# breakout_proto-checkup.net
KiCad netlist of a schematic drawn in EAGLE
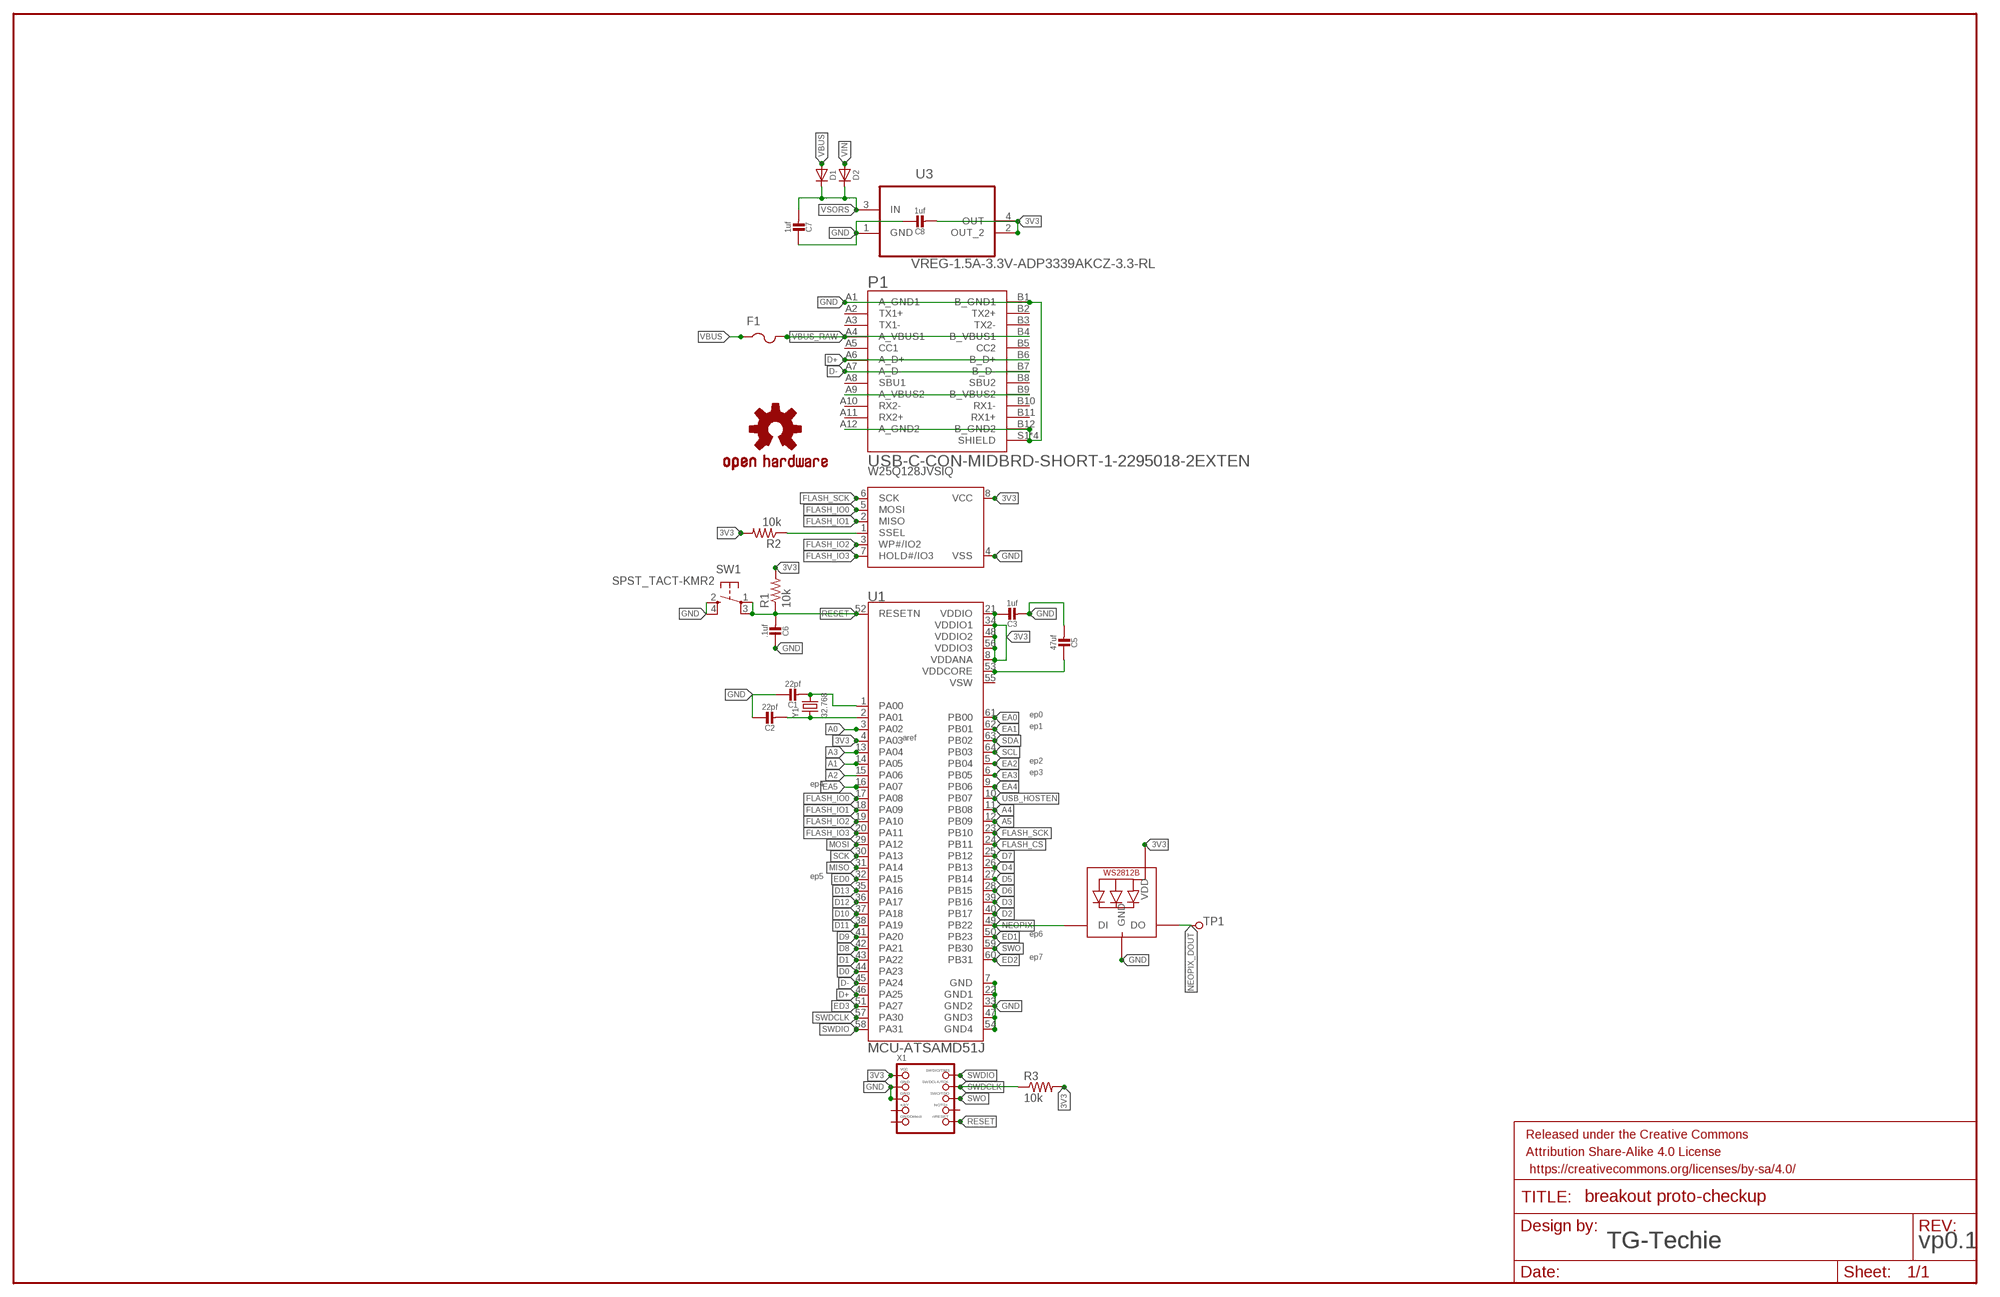
[diagram p0: schematic, sheet 1]

(export (version "E")
  (design (tool "Eeschema 10.0.6"))
  (components
    (comp (ref "C1")
      (value "22pf")
      (footprint "eagle-import:MICROBUILDER__0805")
      (libsource (lib "eagle-import") (part "C-US__0805"))
    )
    (comp (ref "C2")
      (value "22pf")
      (footprint "eagle-import:MICROBUILDER__0805")
      (libsource (lib "eagle-import") (part "C-US__0805"))
    )
    (comp (ref "C3")
      (value "1uf")
      (footprint "eagle-import:MICROBUILDER__0805")
      (libsource (lib "eagle-import") (part "C-US__0805"))
    )
    (comp (ref "C5")
      (value "47uf")
      (footprint "eagle-import:MICROBUILDER__0805")
      (libsource (lib "eagle-import") (part "C-US__0805"))
    )
    (comp (ref "C6")
      (value ".1uf")
      (footprint "eagle-import:MICROBUILDER__0805")
      (libsource (lib "eagle-import") (part "C-US__0805"))
    )
    (comp (ref "C7")
      (value "1uf")
      (footprint "eagle-import:MICROBUILDER__0805")
      (libsource (lib "eagle-import") (part "C-US__0805"))
    )
    (comp (ref "C8")
      (value "1uf")
      (footprint "eagle-import:MICROBUILDER__0805")
      (libsource (lib "eagle-import") (part "C-US__0805"))
    )
    (comp (ref "D1")
      (value "DIODESOD-123")
      (footprint "eagle-import:SOD-123")
      (libsource (lib "eagle-import") (part "DIODESOD-123"))
    )
    (comp (ref "D2")
      (value "DIODESOD-123")
      (footprint "eagle-import:SOD-123")
      (libsource (lib "eagle-import") (part "DIODESOD-123"))
    )
    (comp (ref "F1")
      (value "PTCFUSE-1206")
      (footprint "eagle-import:R1206")
      (libsource (lib "eagle-import") (part "PTCFUSE-1206"))
    )
    (comp (ref "FRAME1")
      (value "FRAME-LEDGER")
      (footprint "eagle-import:CREATIVE_COMMONS")
      (libsource (lib "eagle-import") (part "FRAME-LEDGER"))
    )
    (comp (ref "LED1")
      (value "LED-NEO-WS2812B3535")
      (footprint "eagle-import:LED3535")
      (libsource (lib "eagle-import") (part "LED-NEO-WS2812B3535"))
    )
    (comp (ref "LOGO1")
      (value "OSHW-LOGOMINI")
      (footprint "eagle-import:OSHW-LOGO-MINI")
      (libsource (lib "eagle-import") (part "OSHW-LOGOMINI"))
    )
    (comp (ref "P1")
      (value "USB-C-CON-MIDBRD-SHORT-1-2295018-2EXTEN")
      (footprint "eagle-import:TE_1-2295018-2_EXTEN")
      (libsource (lib "eagle-import") (part "USB-C-CON-MIDBRD-SHORT-1-2295018-2EXTEN"))
    )
    (comp (ref "R1")
      (value "10k")
      (footprint "eagle-import:R0805")
      (libsource (lib "eagle-import") (part "R-US_R0805"))
    )
    (comp (ref "R2")
      (value "10k")
      (footprint "eagle-import:R0805")
      (libsource (lib "eagle-import") (part "R-US_R0805"))
    )
    (comp (ref "R3")
      (value "10k")
      (footprint "eagle-import:R0805")
      (libsource (lib "eagle-import") (part "R-US_R0805"))
    )
    (comp (ref "SW1")
      (value "SPST_TACT-KMR2")
      (footprint "eagle-import:KMR2")
      (libsource (lib "eagle-import") (part "SPST_TACT-KMR2"))
    )
    (comp (ref "TP1")
      (value "TESTPOINT_1X1")
      (footprint "eagle-import:1X1_POGO")
      (libsource (lib "eagle-import") (part "TESTPOINT_1X1"))
    )
    (comp (ref "U1")
      (value "MCU-ATSAMD51J")
      (footprint "eagle-import:QFP50P1200X1200X120-64N")
      (fields (field (name "MF") "Microchip") (field (name "MP") "ATSAMD51J20A-AU"))
      (libsource (lib "eagle-import") (part "MCU-ATSAMD51J"))
    )
    (comp (ref "U3")
      (value "VREG-1.5A-3.3V-ADP3339AKCZ-3.3-RL")
      (footprint "eagle-import:SOT230P700X180-4N")
      (fields (field (name "MF") "Analog Devices") (field (name "MP") "ADP3339AKCZ-3.3-RL"))
      (libsource (lib "eagle-import") (part "VREG-1.5A-3.3V-ADP3339AKCZ-3.3-RL"))
    )
    (comp (ref "W25Q128JVSIQ")
      (value "FLASH-SPI-SOIC8208MIL")
      (footprint "eagle-import:SOIC8_208MIL")
      (libsource (lib "eagle-import") (part "FLASH-SPI-SOIC8208MIL"))
    )
    (comp (ref "X1")
      (value "INTRFC-JTAG-CORTEXBOXPOSTS")
      (footprint "eagle-import:2X05_1.27MM_BOX_POSTS")
      (libsource (lib "eagle-import") (part "INTRFC-JTAG-CORTEXBOXPOSTS"))
    )
    (comp (ref "Y1")
      (value "32.768")
      (footprint "eagle-import:MICROBUILDER_CRYSTAL_4.9X1.8")
      (libsource (lib "eagle-import") (part "XTAL_ADA4.9X1.8"))
    )
  )
  (nets
    (net (code "1") (name "/VSW") (class "Default")
      (node (ref "U1") (pin "55") (pinfunction "VSW_55") (pintype "power_in"))
    )
    (net (code "2") (name "3V3") (class "Default")
      (node (ref "C3") (pin "1") (pinfunction "1_1") (pintype "passive"))
      (node (ref "C8") (pin "2") (pinfunction "2_2") (pintype "passive"))
      (node (ref "LED1") (pin "2") (pinfunction "VDD_2") (pintype "power_in"))
      (node (ref "R1") (pin "2") (pinfunction "2_2") (pintype "passive"))
      (node (ref "R2") (pin "2") (pinfunction "2_2") (pintype "passive"))
      (node (ref "R3") (pin "2") (pinfunction "2_2") (pintype "passive"))
      (node (ref "U1") (pin "21") (pinfunction "VDDIO_21") (pintype "power_in"))
      (node (ref "U1") (pin "34") (pinfunction "VDDIO1_34") (pintype "power_in"))
      (node (ref "U1") (pin "4") (pinfunction "PA03_4") (pintype "bidirectional"))
      (node (ref "U1") (pin "48") (pinfunction "VDDIO2_48") (pintype "power_in"))
      (node (ref "U1") (pin "56") (pinfunction "VDDIO3_56") (pintype "power_in"))
      (node (ref "U1") (pin "8") (pinfunction "VDDANA_8") (pintype "power_in"))
      (node (ref "U3") (pin "2") (pinfunction "OUT_2_2") (pintype "output"))
      (node (ref "U3") (pin "4") (pinfunction "OUT_4") (pintype "output"))
      (node (ref "W25Q128JVSIQ") (pin "8") (pinfunction "VCC_8") (pintype "bidirectional"))
      (node (ref "X1") (pin "1") (pinfunction "VCC_1") (pintype "power_in"))
    )
    (net (code "3") (name "A0") (class "Default")
      (node (ref "U1") (pin "3") (pinfunction "PA02_3") (pintype "bidirectional"))
    )
    (net (code "4") (name "A1") (class "Default")
      (node (ref "U1") (pin "14") (pinfunction "PA05_14") (pintype "bidirectional"))
    )
    (net (code "5") (name "A2") (class "Default")
      (node (ref "U1") (pin "15") (pinfunction "PA06_15") (pintype "bidirectional"))
    )
    (net (code "6") (name "A3") (class "Default")
      (node (ref "U1") (pin "13") (pinfunction "PA04_13") (pintype "bidirectional"))
    )
    (net (code "7") (name "A4") (class "Default")
      (node (ref "U1") (pin "11") (pinfunction "PB08_11") (pintype "bidirectional"))
    )
    (net (code "8") (name "A5") (class "Default")
      (node (ref "U1") (pin "12") (pinfunction "PB09_12") (pintype "bidirectional"))
    )
    (net (code "9") (name "D+") (class "Default")
      (node (ref "P1") (pin "A6") (pinfunction "A_D+_A6") (pintype "passive"))
      (node (ref "P1") (pin "B6") (pinfunction "B_D+_B6") (pintype "passive"))
      (node (ref "U1") (pin "46") (pinfunction "PA25_46") (pintype "bidirectional"))
    )
    (net (code "10") (name "D-") (class "Default")
      (node (ref "P1") (pin "A7") (pinfunction "A_D-_A7") (pintype "passive"))
      (node (ref "P1") (pin "B7") (pinfunction "B_D-_B7") (pintype "passive"))
      (node (ref "U1") (pin "45") (pinfunction "PA24_45") (pintype "bidirectional"))
    )
    (net (code "11") (name "D0") (class "Default")
      (node (ref "U1") (pin "44") (pinfunction "PA23_44") (pintype "bidirectional"))
    )
    (net (code "12") (name "D1") (class "Default")
      (node (ref "U1") (pin "43") (pinfunction "PA22_43") (pintype "bidirectional"))
    )
    (net (code "13") (name "D2") (class "Default")
      (node (ref "U1") (pin "40") (pinfunction "PB17_40") (pintype "bidirectional"))
    )
    (net (code "14") (name "D3") (class "Default")
      (node (ref "U1") (pin "39") (pinfunction "PB16_39") (pintype "bidirectional"))
    )
    (net (code "15") (name "D4") (class "Default")
      (node (ref "U1") (pin "26") (pinfunction "PB13_26") (pintype "bidirectional"))
    )
    (net (code "16") (name "D5") (class "Default")
      (node (ref "U1") (pin "27") (pinfunction "PB14_27") (pintype "bidirectional"))
    )
    (net (code "17") (name "D6") (class "Default")
      (node (ref "U1") (pin "28") (pinfunction "PB15_28") (pintype "bidirectional"))
    )
    (net (code "18") (name "D7") (class "Default")
      (node (ref "U1") (pin "25") (pinfunction "PB12_25") (pintype "bidirectional"))
    )
    (net (code "19") (name "D8") (class "Default")
      (node (ref "U1") (pin "42") (pinfunction "PA21_42") (pintype "bidirectional"))
    )
    (net (code "20") (name "D9") (class "Default")
      (node (ref "U1") (pin "41") (pinfunction "PA20_41") (pintype "bidirectional"))
    )
    (net (code "21") (name "D10") (class "Default")
      (node (ref "U1") (pin "37") (pinfunction "PA18_37") (pintype "bidirectional"))
    )
    (net (code "22") (name "D11") (class "Default")
      (node (ref "U1") (pin "38") (pinfunction "PA19_38") (pintype "bidirectional"))
    )
    (net (code "23") (name "D12") (class "Default")
      (node (ref "U1") (pin "36") (pinfunction "PA17_36") (pintype "bidirectional"))
    )
    (net (code "24") (name "D13") (class "Default")
      (node (ref "U1") (pin "35") (pinfunction "PA16_35") (pintype "bidirectional"))
    )
    (net (code "25") (name "EA0") (class "Default")
      (node (ref "U1") (pin "61") (pinfunction "PB00_61") (pintype "bidirectional"))
    )
    (net (code "26") (name "EA1") (class "Default")
      (node (ref "U1") (pin "62") (pinfunction "PB01_62") (pintype "bidirectional"))
    )
    (net (code "27") (name "EA2") (class "Default")
      (node (ref "U1") (pin "5") (pinfunction "PB04_5") (pintype "bidirectional"))
    )
    (net (code "28") (name "EA3") (class "Default")
      (node (ref "U1") (pin "6") (pinfunction "PB05_6") (pintype "bidirectional"))
    )
    (net (code "29") (name "EA4") (class "Default")
      (node (ref "U1") (pin "9") (pinfunction "PB06_9") (pintype "bidirectional"))
    )
    (net (code "30") (name "EA5") (class "Default")
      (node (ref "U1") (pin "16") (pinfunction "PA07_16") (pintype "bidirectional"))
    )
    (net (code "31") (name "ED0") (class "Default")
      (node (ref "U1") (pin "32") (pinfunction "PA15_32") (pintype "bidirectional"))
    )
    (net (code "32") (name "ED1") (class "Default")
      (node (ref "U1") (pin "50") (pinfunction "PB23_50") (pintype "bidirectional"))
    )
    (net (code "33") (name "ED2") (class "Default")
      (node (ref "U1") (pin "60") (pinfunction "PB31_60") (pintype "bidirectional"))
    )
    (net (code "34") (name "ED3") (class "Default")
      (node (ref "U1") (pin "51") (pinfunction "PA27_51") (pintype "bidirectional"))
    )
    (net (code "35") (name "FLASH_CS") (class "Default")
      (node (ref "U1") (pin "24") (pinfunction "PB11_24") (pintype "bidirectional"))
    )
    (net (code "36") (name "FLASH_IO0") (class "Default")
      (node (ref "U1") (pin "17") (pinfunction "PA08_17") (pintype "bidirectional"))
      (node (ref "W25Q128JVSIQ") (pin "5") (pinfunction "MOSI_5") (pintype "bidirectional"))
    )
    (net (code "37") (name "FLASH_IO1") (class "Default")
      (node (ref "U1") (pin "18") (pinfunction "PA09_18") (pintype "bidirectional"))
      (node (ref "W25Q128JVSIQ") (pin "2") (pinfunction "MISO_2") (pintype "bidirectional"))
    )
    (net (code "38") (name "FLASH_IO2") (class "Default")
      (node (ref "U1") (pin "19") (pinfunction "PA10_19") (pintype "bidirectional"))
      (node (ref "W25Q128JVSIQ") (pin "3") (pinfunction "WP#/IO2_3") (pintype "bidirectional"))
    )
    (net (code "39") (name "FLASH_IO3") (class "Default")
      (node (ref "U1") (pin "20") (pinfunction "PA11_20") (pintype "bidirectional"))
      (node (ref "W25Q128JVSIQ") (pin "7") (pinfunction "HOLD#/IO3_7") (pintype "bidirectional"))
    )
    (net (code "40") (name "FLASH_SCK") (class "Default")
      (node (ref "U1") (pin "23") (pinfunction "PB10_23") (pintype "bidirectional"))
      (node (ref "W25Q128JVSIQ") (pin "6") (pinfunction "SCK_6") (pintype "bidirectional"))
    )
    (net (code "41") (name "GND") (class "Default")
      (node (ref "C1") (pin "1") (pinfunction "1_1") (pintype "passive"))
      (node (ref "C2") (pin "1") (pinfunction "1_1") (pintype "passive"))
      (node (ref "C3") (pin "2") (pinfunction "2_2") (pintype "passive"))
      (node (ref "C5") (pin "2") (pinfunction "2_2") (pintype "passive"))
      (node (ref "C6") (pin "1") (pinfunction "1_1") (pintype "passive"))
      (node (ref "C7") (pin "1") (pinfunction "1_1") (pintype "passive"))
      (node (ref "C8") (pin "1") (pinfunction "1_1") (pintype "passive"))
      (node (ref "LED1") (pin "4") (pinfunction "GND_4") (pintype "power_in"))
      (node (ref "P1") (pin "A1") (pinfunction "A_GND1_A1") (pintype "passive"))
      (node (ref "P1") (pin "A12") (pinfunction "A_GND2_A12") (pintype "passive"))
      (node (ref "P1") (pin "B1") (pinfunction "B_GND1_B1") (pintype "passive"))
      (node (ref "P1") (pin "B12") (pinfunction "B_GND2_B12") (pintype "passive"))
      (node (ref "P1") (pin "S1") (pinfunction "SHIELD_S1") (pintype "passive"))
      (node (ref "P1") (pin "S2") (pinfunction "SHIELD_S2") (pintype "passive"))
      (node (ref "P1") (pin "S3") (pinfunction "SHIELD_S3") (pintype "passive"))
      (node (ref "P1") (pin "S4") (pinfunction "SHIELD_S4") (pintype "passive"))
      (node (ref "SW1") (pin "2") (pinfunction "S_2") (pintype "passive"))
      (node (ref "SW1") (pin "4") (pinfunction "S1_4") (pintype "passive"))
      (node (ref "U1") (pin "22") (pinfunction "GND1_22") (pintype "power_in"))
      (node (ref "U1") (pin "33") (pinfunction "GND2_33") (pintype "power_in"))
      (node (ref "U1") (pin "47") (pinfunction "GND3_47") (pintype "power_in"))
      (node (ref "U1") (pin "54") (pinfunction "GND4_54") (pintype "power_in"))
      (node (ref "U1") (pin "7") (pinfunction "GND_7") (pintype "power_in"))
      (node (ref "U3") (pin "1") (pinfunction "GND_1") (pintype "passive"))
      (node (ref "W25Q128JVSIQ") (pin "4") (pinfunction "VSS_4") (pintype "bidirectional"))
      (node (ref "X1") (pin "3") (pinfunction "GND_3") (pintype "power_in"))
      (node (ref "X1") (pin "5") (pinfunction "GND_5") (pintype "power_in"))
    )
    (net (code "42") (name "MISO") (class "Default")
      (node (ref "U1") (pin "31") (pinfunction "PA14_31") (pintype "bidirectional"))
    )
    (net (code "43") (name "MOSI") (class "Default")
      (node (ref "U1") (pin "29") (pinfunction "PA12_29") (pintype "bidirectional"))
    )
    (net (code "44") (name "NEOPIX") (class "Default")
      (node (ref "LED1") (pin "1") (pinfunction "DI_1") (pintype "input"))
      (node (ref "U1") (pin "49") (pinfunction "PB22_49") (pintype "bidirectional"))
    )
    (net (code "45") (name "NEOPIX_DOUT") (class "Default")
      (node (ref "LED1") (pin "3") (pinfunction "DO_3") (pintype "output"))
      (node (ref "TP1") (pin "1") (pinfunction "P1_1") (pintype "bidirectional"))
    )
    (net (code "46") (name "Net-(P1-A_VBUS2)") (class "Default")
      (node (ref "P1") (pin "A9") (pinfunction "A_VBUS2_A9") (pintype "passive"))
      (node (ref "P1") (pin "B9") (pinfunction "B_VBUS2_B9") (pintype "passive"))
    )
    (net (code "47") (name "Net-(U1-PA00)") (class "Default")
      (node (ref "C1") (pin "2") (pinfunction "2_2") (pintype "passive"))
      (node (ref "U1") (pin "1") (pinfunction "PA00_1") (pintype "bidirectional"))
      (node (ref "Y1") (pin "2") (pinfunction "2_2") (pintype "passive"))
    )
    (net (code "48") (name "Net-(U1-PA01)") (class "Default")
      (node (ref "C2") (pin "2") (pinfunction "2_2") (pintype "passive"))
      (node (ref "U1") (pin "2") (pinfunction "PA01_2") (pintype "bidirectional"))
      (node (ref "Y1") (pin "1") (pinfunction "1_1") (pintype "passive"))
    )
    (net (code "49") (name "Net-(U1-VDDCORE)") (class "Default")
      (node (ref "C5") (pin "1") (pinfunction "1_1") (pintype "passive"))
      (node (ref "U1") (pin "53") (pinfunction "VDDCORE_53") (pintype "power_in"))
    )
    (net (code "50") (name "Net-(W25Q128JVSIQ-SSEL)") (class "Default")
      (node (ref "R2") (pin "1") (pinfunction "1_1") (pintype "passive"))
      (node (ref "W25Q128JVSIQ") (pin "1") (pinfunction "SSEL_1") (pintype "bidirectional"))
    )
    (net (code "51") (name "RESET") (class "Default")
      (node (ref "C6") (pin "2") (pinfunction "2_2") (pintype "passive"))
      (node (ref "R1") (pin "1") (pinfunction "1_1") (pintype "passive"))
      (node (ref "SW1") (pin "1") (pinfunction "P_1") (pintype "passive"))
      (node (ref "SW1") (pin "3") (pinfunction "P1_3") (pintype "passive"))
      (node (ref "U1") (pin "52") (pinfunction "RESETN_52") (pintype "input"))
      (node (ref "X1") (pin "10") (pinfunction "NRESET_10") (pintype "bidirectional"))
    )
    (net (code "52") (name "SCK") (class "Default")
      (node (ref "U1") (pin "30") (pinfunction "PA13_30") (pintype "bidirectional"))
    )
    (net (code "53") (name "SCL") (class "Default")
      (node (ref "U1") (pin "64") (pinfunction "PB03_64") (pintype "bidirectional"))
    )
    (net (code "54") (name "SDA") (class "Default")
      (node (ref "U1") (pin "63") (pinfunction "PB02_63") (pintype "bidirectional"))
    )
    (net (code "55") (name "SWDCLK") (class "Default")
      (node (ref "R3") (pin "1") (pinfunction "1_1") (pintype "passive"))
      (node (ref "U1") (pin "57") (pinfunction "PA30_57") (pintype "bidirectional"))
      (node (ref "X1") (pin "4") (pinfunction "SWDCLK_4") (pintype "bidirectional"))
    )
    (net (code "56") (name "SWDIO") (class "Default")
      (node (ref "U1") (pin "58") (pinfunction "PA31_58") (pintype "bidirectional"))
      (node (ref "X1") (pin "2") (pinfunction "SWDIO_2") (pintype "bidirectional"))
    )
    (net (code "57") (name "SWO") (class "Default")
      (node (ref "U1") (pin "59") (pinfunction "PB30_59") (pintype "bidirectional"))
      (node (ref "X1") (pin "6") (pinfunction "SWO_6") (pintype "bidirectional"))
    )
    (net (code "58") (name "USB_HOSTEN") (class "Default")
      (node (ref "U1") (pin "10") (pinfunction "PB07_10") (pintype "bidirectional"))
    )
    (net (code "59") (name "VBUS") (class "Default")
      (node (ref "D1") (pin "A") (pinfunction "A_A") (pintype "passive"))
      (node (ref "F1") (pin "1") (pinfunction "1_1") (pintype "passive"))
    )
    (net (code "60") (name "VBUS_RAW") (class "Default")
      (node (ref "F1") (pin "2") (pinfunction "2_2") (pintype "passive"))
      (node (ref "P1") (pin "A4") (pinfunction "A_VBUS1_A4") (pintype "passive"))
      (node (ref "P1") (pin "B4") (pinfunction "B_VBUS1_B4") (pintype "passive"))
    )
    (net (code "61") (name "VIN") (class "Default")
      (node (ref "D2") (pin "A") (pinfunction "A_A") (pintype "passive"))
    )
    (net (code "62") (name "VSORS") (class "Default")
      (node (ref "C7") (pin "2") (pinfunction "2_2") (pintype "passive"))
      (node (ref "D1") (pin "C") (pinfunction "C_C") (pintype "passive"))
      (node (ref "D2") (pin "C") (pinfunction "C_C") (pintype "passive"))
      (node (ref "U3") (pin "3") (pinfunction "IN_3") (pintype "input"))
    )
    (net (code "63") (name "unconnected-(P1-CC1-PadA5)") (class "Default")
      (node (ref "P1") (pin "A5") (pinfunction "CC1_A5") (pintype "passive"))
    )
    (net (code "64") (name "unconnected-(P1-CC2-PadB5)") (class "Default")
      (node (ref "P1") (pin "B5") (pinfunction "CC2_B5") (pintype "passive"))
    )
    (net (code "65") (name "unconnected-(P1-RX1+-PadB11)") (class "Default")
      (node (ref "P1") (pin "B11") (pinfunction "RX1+_B11") (pintype "passive"))
    )
    (net (code "66") (name "unconnected-(P1-RX1--PadB10)") (class "Default")
      (node (ref "P1") (pin "B10") (pinfunction "RX1-_B10") (pintype "passive"))
    )
    (net (code "67") (name "unconnected-(P1-RX2+-PadA11)") (class "Default")
      (node (ref "P1") (pin "A11") (pinfunction "RX2+_A11") (pintype "passive"))
    )
    (net (code "68") (name "unconnected-(P1-RX2--PadA10)") (class "Default")
      (node (ref "P1") (pin "A10") (pinfunction "RX2-_A10") (pintype "passive"))
    )
    (net (code "69") (name "unconnected-(P1-SBU1-PadA8)") (class "Default")
      (node (ref "P1") (pin "A8") (pinfunction "SBU1_A8") (pintype "passive"))
    )
    (net (code "70") (name "unconnected-(P1-SBU2-PadB8)") (class "Default")
      (node (ref "P1") (pin "B8") (pinfunction "SBU2_B8") (pintype "passive"))
    )
    (net (code "71") (name "unconnected-(P1-TX1+-PadA2)") (class "Default")
      (node (ref "P1") (pin "A2") (pinfunction "TX1+_A2") (pintype "passive"))
    )
    (net (code "72") (name "unconnected-(P1-TX1--PadA3)") (class "Default")
      (node (ref "P1") (pin "A3") (pinfunction "TX1-_A3") (pintype "passive"))
    )
    (net (code "73") (name "unconnected-(P1-TX2+-PadB2)") (class "Default")
      (node (ref "P1") (pin "B2") (pinfunction "TX2+_B2") (pintype "passive"))
    )
    (net (code "74") (name "unconnected-(P1-TX2--PadB3)") (class "Default")
      (node (ref "P1") (pin "B3") (pinfunction "TX2-_B3") (pintype "passive"))
    )
    (net (code "75") (name "unconnected-(X1-GNDDETECT-Pad9)") (class "Default")
      (node (ref "X1") (pin "9") (pinfunction "GNDDETECT_9") (pintype "bidirectional"))
    )
    (net (code "76") (name "unconnected-(X1-KEY-Pad7)") (class "Default")
      (node (ref "X1") (pin "7") (pinfunction "KEY_7") (pintype "bidirectional"))
    )
    (net (code "77") (name "unconnected-(X1-TDI-Pad8)") (class "Default")
      (node (ref "X1") (pin "8") (pinfunction "TDI_8") (pintype "bidirectional"))
    )
  )
)
